# CONNECTORS.net
KiCad netlist of a schematic drawn in Altium Designer
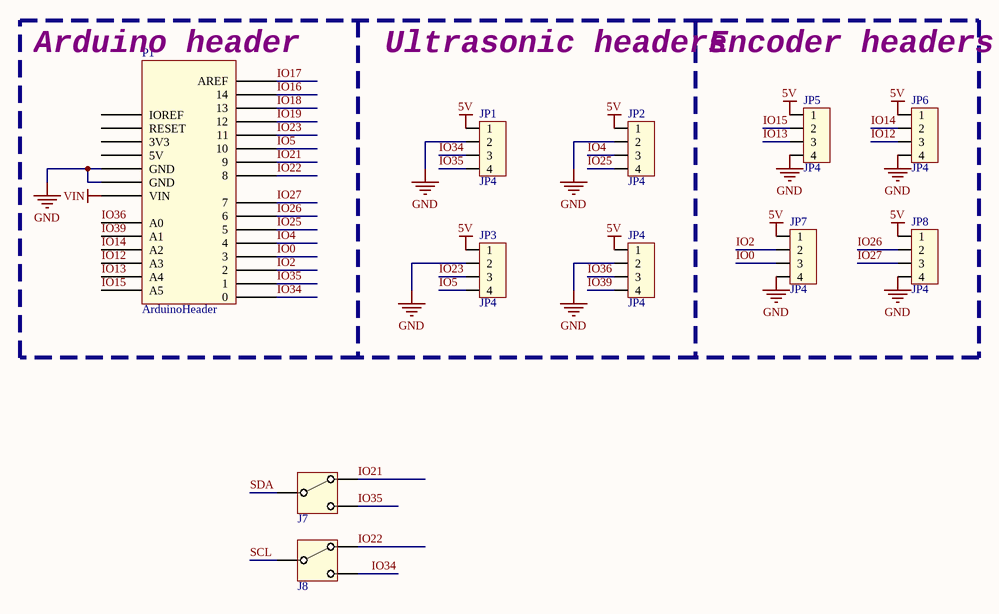
[diagram p0: CONNECTORS.SchDoc]

(export (version "E")
  (design (tool "Eeschema 10.0.6"))
  (components
    (comp (ref "J7")
      (value "JUMPER-SOLDER-3WAY-BOTTOM")
      (footprint "JUMPER-SOLDER-3WAY-BOTTOM")
      (libsource (lib "electronpowered") (part "JUMPER-SOLDER-3WAY-BOTTOM"))
    )
    (comp (ref "J8")
      (value "JUMPER-SOLDER-3WAY-BOTTOM")
      (footprint "JUMPER-SOLDER-3WAY-BOTTOM")
      (libsource (lib "electronpowered") (part "JUMPER-SOLDER-3WAY-BOTTOM"))
    )
    (comp (ref "JP1")
      (value "JP4")
      (footprint "CON4")
      (description "Connector 4")
      (libsource (lib "My Library") (part "Con4"))
    )
    (comp (ref "JP2")
      (value "JP4")
      (footprint "CON4")
      (description "Connector 4")
      (libsource (lib "My Library") (part "Con4"))
    )
    (comp (ref "JP3")
      (value "JP4")
      (footprint "CON4")
      (description "Connector 4")
      (libsource (lib "My Library") (part "Con4"))
    )
    (comp (ref "JP4")
      (value "JP4")
      (footprint "CON4")
      (description "Connector 4")
      (libsource (lib "My Library") (part "Con4"))
    )
    (comp (ref "JP5")
      (value "JP4")
      (footprint "CON4")
      (description "Connector 4")
      (libsource (lib "My Library") (part "Con4"))
    )
    (comp (ref "JP6")
      (value "JP4")
      (footprint "CON4")
      (description "Connector 4")
      (libsource (lib "My Library") (part "Con4"))
    )
    (comp (ref "JP7")
      (value "JP4")
      (footprint "CON4")
      (description "Connector 4")
      (libsource (lib "My Library") (part "Con4"))
    )
    (comp (ref "JP8")
      (value "JP4")
      (footprint "CON4")
      (description "Connector 4")
      (libsource (lib "My Library") (part "Con4"))
    )
    (comp (ref "P1")
      (value "ArduinoHeader")
      (footprint "Arduino_header")
      (libsource (lib "electronpowered") (part "ArduinoHeader"))
    )
  )
  (nets
    (net (code "1") (name "/IO0") (class "Default")
      (node (ref "JP7") (pin "3") (pinfunction "3_3") (pintype "passive"))
      (node (ref "P1") (pin "3") (pinfunction "3_3") (pintype "passive"))
    )
    (net (code "2") (name "/IO2") (class "Default")
      (node (ref "JP7") (pin "2") (pinfunction "2_2") (pintype "passive"))
      (node (ref "P1") (pin "2") (pinfunction "2_2") (pintype "passive"))
    )
    (net (code "3") (name "/IO4") (class "Default")
      (node (ref "JP2") (pin "3") (pinfunction "3_3") (pintype "passive"))
      (node (ref "P1") (pin "4") (pinfunction "4_4") (pintype "passive"))
    )
    (net (code "4") (name "/IO5") (class "Default")
      (node (ref "JP3") (pin "4") (pinfunction "4_4") (pintype "passive"))
      (node (ref "P1") (pin "10") (pinfunction "10_10") (pintype "passive"))
    )
    (net (code "5") (name "/IO12") (class "Default")
      (node (ref "JP6") (pin "3") (pinfunction "3_3") (pintype "passive"))
      (node (ref "P1") (pin "A3") (pinfunction "A3_A3") (pintype "passive"))
    )
    (net (code "6") (name "/IO13") (class "Default")
      (node (ref "JP5") (pin "3") (pinfunction "3_3") (pintype "passive"))
      (node (ref "P1") (pin "A4") (pinfunction "A4_A4") (pintype "passive"))
    )
    (net (code "7") (name "/IO14") (class "Default")
      (node (ref "JP6") (pin "2") (pinfunction "2_2") (pintype "passive"))
      (node (ref "P1") (pin "A2") (pinfunction "A2_A2") (pintype "passive"))
    )
    (net (code "8") (name "/IO15") (class "Default")
      (node (ref "JP5") (pin "2") (pinfunction "2_2") (pintype "passive"))
      (node (ref "P1") (pin "A5") (pinfunction "A5_A5") (pintype "passive"))
    )
    (net (code "9") (name "/IO16") (class "Default")
      (node (ref "P1") (pin "14") (pinfunction "14_14") (pintype "passive"))
    )
    (net (code "10") (name "/IO17") (class "Default")
      (node (ref "P1") (pin "AREF") (pinfunction "AREF_AREF") (pintype "passive"))
    )
    (net (code "11") (name "/IO18") (class "Default")
      (node (ref "P1") (pin "13") (pinfunction "13_13") (pintype "passive"))
    )
    (net (code "12") (name "/IO19") (class "Default")
      (node (ref "P1") (pin "12") (pinfunction "12_12") (pintype "passive"))
    )
    (net (code "13") (name "/IO21") (class "Default")
      (node (ref "J7") (pin "0") (pinfunction "0_0") (pintype "passive"))
      (node (ref "P1") (pin "9") (pinfunction "9_9") (pintype "passive"))
    )
    (net (code "14") (name "/IO22") (class "Default")
      (node (ref "J8") (pin "0") (pinfunction "0_0") (pintype "passive"))
      (node (ref "P1") (pin "8") (pinfunction "8_8") (pintype "passive"))
    )
    (net (code "15") (name "/IO23") (class "Default")
      (node (ref "JP3") (pin "3") (pinfunction "3_3") (pintype "passive"))
      (node (ref "P1") (pin "11") (pinfunction "11_11") (pintype "passive"))
    )
    (net (code "16") (name "/IO25") (class "Default")
      (node (ref "JP2") (pin "4") (pinfunction "4_4") (pintype "passive"))
      (node (ref "P1") (pin "5") (pinfunction "5_5") (pintype "passive"))
    )
    (net (code "17") (name "/IO26") (class "Default")
      (node (ref "JP8") (pin "2") (pinfunction "2_2") (pintype "passive"))
      (node (ref "P1") (pin "6") (pinfunction "6_6") (pintype "passive"))
    )
    (net (code "18") (name "/IO27") (class "Default")
      (node (ref "JP8") (pin "3") (pinfunction "3_3") (pintype "passive"))
      (node (ref "P1") (pin "7") (pinfunction "7_7") (pintype "passive"))
    )
    (net (code "19") (name "/IO34") (class "Default")
      (node (ref "J8") (pin "2") (pinfunction "2_2") (pintype "passive"))
      (node (ref "JP1") (pin "3") (pinfunction "3_3") (pintype "passive"))
      (node (ref "P1") (pin "0") (pinfunction "0_0") (pintype "passive"))
    )
    (net (code "20") (name "/IO35") (class "Default")
      (node (ref "J7") (pin "2") (pinfunction "2_2") (pintype "passive"))
      (node (ref "JP1") (pin "4") (pinfunction "4_4") (pintype "passive"))
      (node (ref "P1") (pin "1") (pinfunction "1_1") (pintype "passive"))
    )
    (net (code "21") (name "/IO36") (class "Default")
      (node (ref "JP4") (pin "3") (pinfunction "3_3") (pintype "passive"))
      (node (ref "P1") (pin "A0") (pinfunction "A0_A0") (pintype "passive"))
    )
    (net (code "22") (name "/IO39") (class "Default")
      (node (ref "JP4") (pin "4") (pinfunction "4_4") (pintype "passive"))
      (node (ref "P1") (pin "A1") (pinfunction "A1_A1") (pintype "passive"))
    )
    (net (code "23") (name "/SCL") (class "Default")
      (node (ref "J8") (pin "1") (pinfunction "1_1") (pintype "passive"))
    )
    (net (code "24") (name "/SDA") (class "Default")
      (node (ref "J7") (pin "1") (pinfunction "1_1") (pintype "passive"))
    )
    (net (code "25") (name "5V") (class "Default")
      (node (ref "JP1") (pin "1") (pinfunction "1_1") (pintype "passive"))
      (node (ref "JP2") (pin "1") (pinfunction "1_1") (pintype "passive"))
      (node (ref "JP3") (pin "1") (pinfunction "1_1") (pintype "passive"))
      (node (ref "JP4") (pin "1") (pinfunction "1_1") (pintype "passive"))
      (node (ref "JP5") (pin "1") (pinfunction "1_1") (pintype "passive"))
      (node (ref "JP6") (pin "1") (pinfunction "1_1") (pintype "passive"))
      (node (ref "JP7") (pin "1") (pinfunction "1_1") (pintype "passive"))
      (node (ref "JP8") (pin "1") (pinfunction "1_1") (pintype "passive"))
    )
    (net (code "26") (name "GND") (class "Default")
      (node (ref "JP1") (pin "2") (pinfunction "2_2") (pintype "passive"))
      (node (ref "JP2") (pin "2") (pinfunction "2_2") (pintype "passive"))
      (node (ref "JP3") (pin "2") (pinfunction "2_2") (pintype "passive"))
      (node (ref "JP4") (pin "2") (pinfunction "2_2") (pintype "passive"))
      (node (ref "JP5") (pin "4") (pinfunction "4_4") (pintype "passive"))
      (node (ref "JP6") (pin "4") (pinfunction "4_4") (pintype "passive"))
      (node (ref "JP7") (pin "4") (pinfunction "4_4") (pintype "passive"))
      (node (ref "JP8") (pin "4") (pinfunction "4_4") (pintype "passive"))
      (node (ref "P1") (pin "GND") (pinfunction "GND_GND") (pintype "passive"))
    )
    (net (code "27") (name "VIN") (class "Default")
      (node (ref "P1") (pin "VIN") (pinfunction "VIN_VIN") (pintype "passive"))
    )
    (net (code "28") (name "unconnected-(P1-Pad3V3)") (class "Default")
      (node (ref "P1") (pin "3V3") (pinfunction "3V3_3V3") (pintype "passive"))
    )
    (net (code "29") (name "unconnected-(P1-Pad5V)") (class "Default")
      (node (ref "P1") (pin "5V") (pinfunction "5V_5V") (pintype "passive"))
    )
    (net (code "30") (name "unconnected-(P1-PadIOREF)") (class "Default")
      (node (ref "P1") (pin "IOREF") (pinfunction "IOREF_IOREF") (pintype "passive"))
    )
    (net (code "31") (name "unconnected-(P1-PadRESET)") (class "Default")
      (node (ref "P1") (pin "RESET") (pinfunction "RESET_RESET") (pintype "passive"))
    )
  )
)
